# 03_USB_TO_UART.net
KiCad netlist of a schematic drawn in Altium Designer
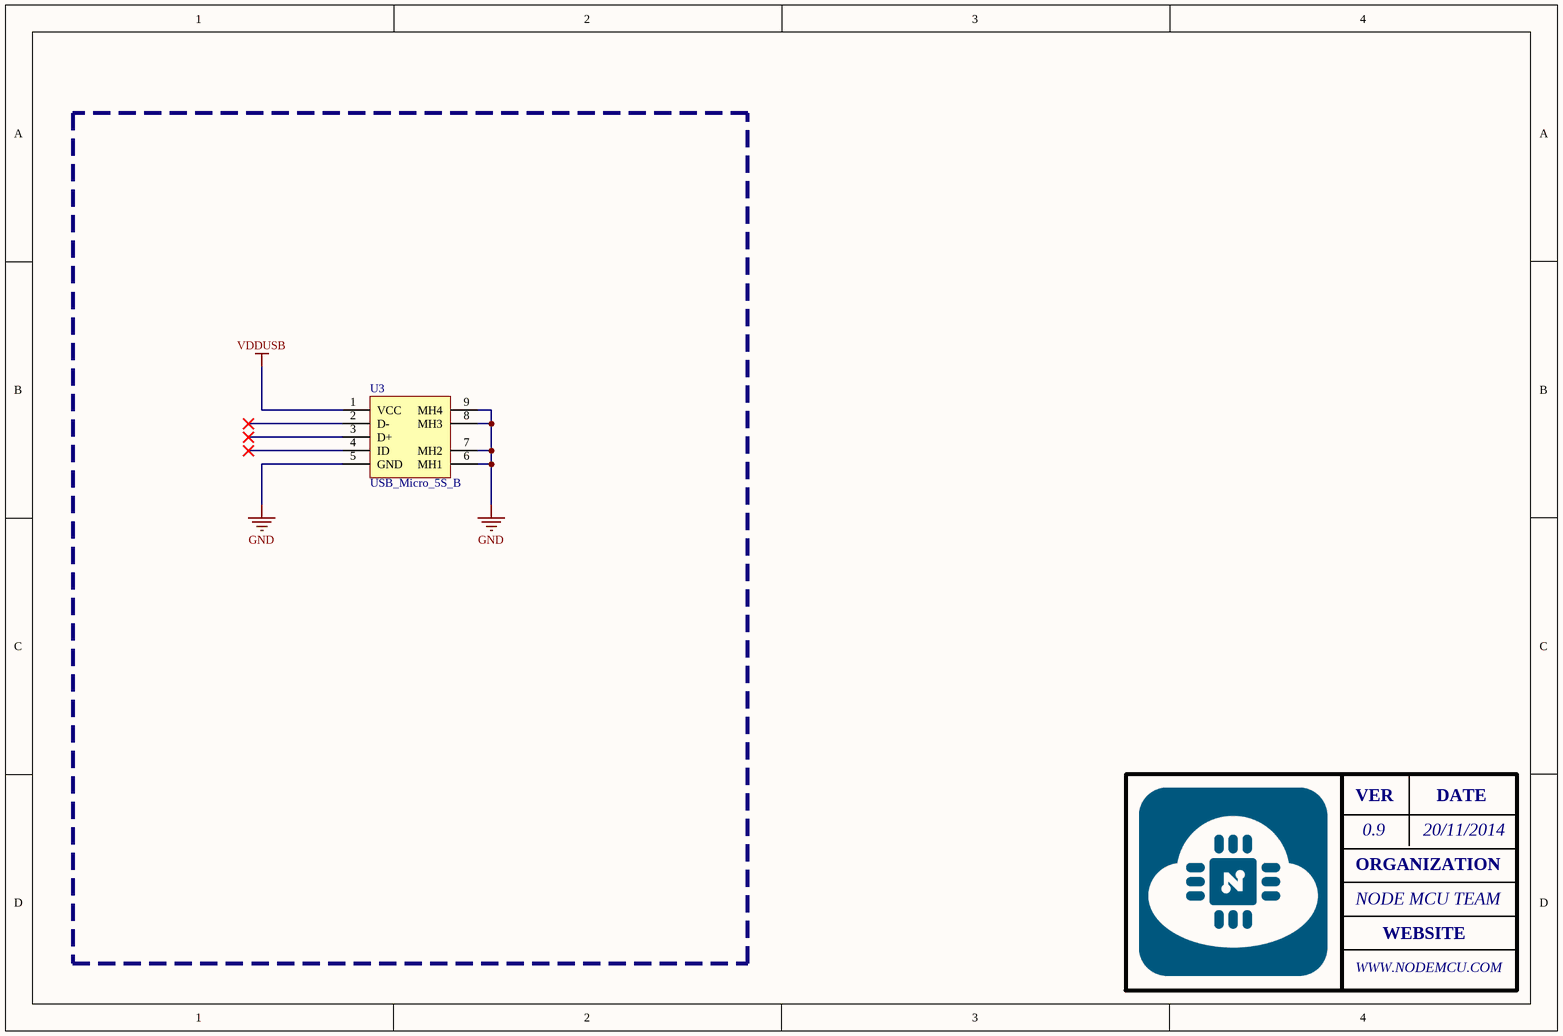
[diagram p0: 03_USB_TO_UART.SchDoc]

(export (version "E")
  (design (tool "Eeschema 10.0.6"))
  (components
    (comp (ref "U3")
      (value "USB_Micro_5S_B")
      (footprint "USB_MICRO_5S_B")
      (description "USB micro female SMT with 4 fixed foot")
      (libsource (lib "Vowstar_Connector") (part "USB_Micro_5S_B"))
    )
  )
  (nets
    (net (code "1") (name "GND") (class "Default")
      (node (ref "U3") (pin "5") (pinfunction "GND_5") (pintype "passive"))
      (node (ref "U3") (pin "6") (pinfunction "MH1_6") (pintype "passive"))
      (node (ref "U3") (pin "7") (pinfunction "MH2_7") (pintype "passive"))
      (node (ref "U3") (pin "8") (pinfunction "MH3_8") (pintype "passive"))
      (node (ref "U3") (pin "9") (pinfunction "MH4_9") (pintype "passive"))
    )
    (net (code "2") (name "VDDUSB") (class "Default")
      (node (ref "U3") (pin "1") (pinfunction "VCC_1") (pintype "passive"))
    )
    (net (code "3") (name "unconnected-(U3-D+-Pad3)") (class "Default")
      (node (ref "U3") (pin "3") (pinfunction "D+_3") (pintype "passive+no_connect"))
    )
    (net (code "4") (name "unconnected-(U3-D--Pad2)") (class "Default")
      (node (ref "U3") (pin "2") (pinfunction "D-_2") (pintype "passive+no_connect"))
    )
    (net (code "5") (name "unconnected-(U3-ID-Pad4)") (class "Default")
      (node (ref "U3") (pin "4") (pinfunction "ID_4") (pintype "passive+no_connect"))
    )
  )
)
